# BuzzerSchematic.net
KiCad netlist of a schematic drawn in EAGLE
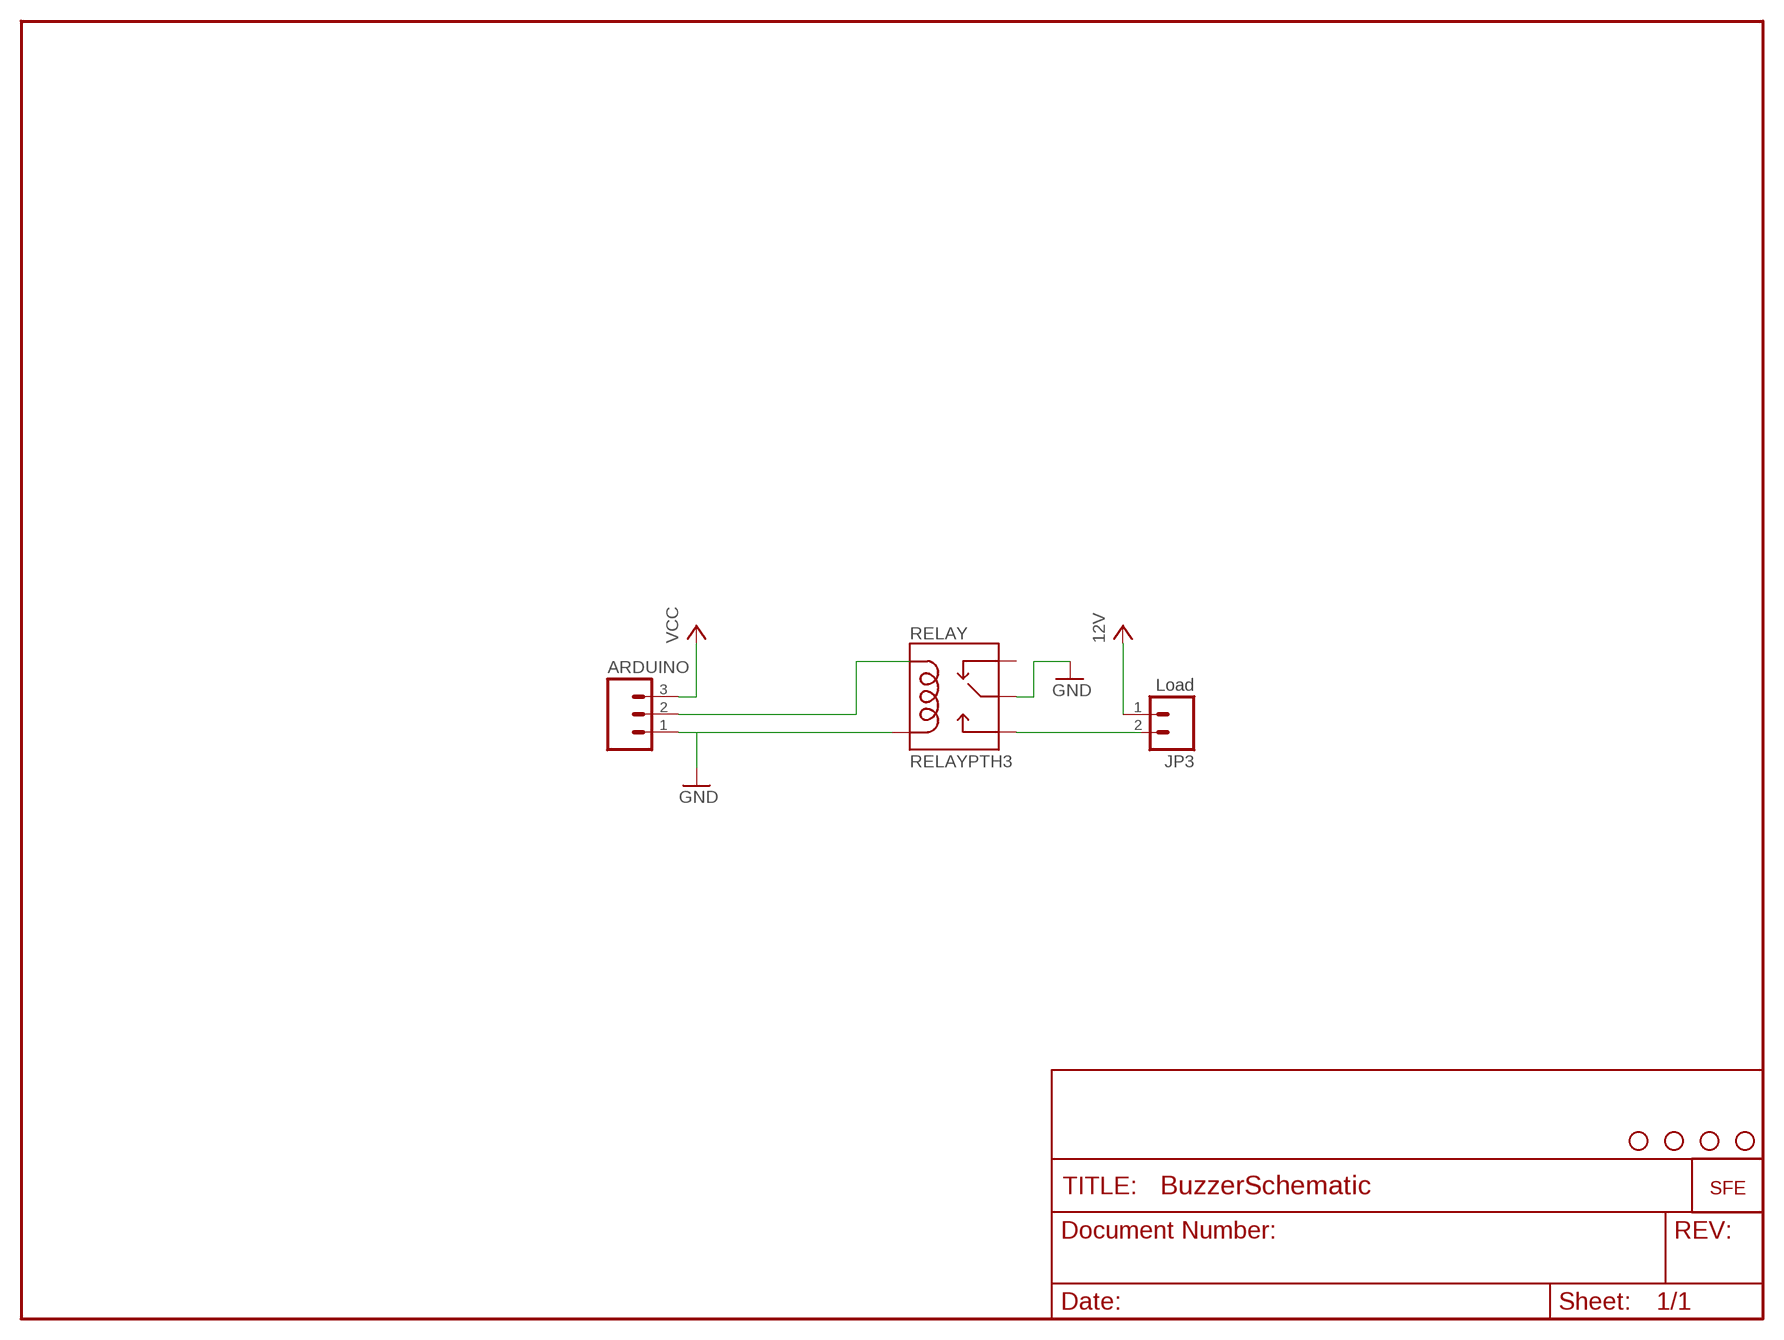
[diagram p0: schematic, sheet 1]

(export (version "E")
  (design (tool "Eeschema 10.0.6"))
  (components
    (comp (ref "ARDUINO")
      (value "M03SCREW")
      (footprint "eagle-import:SCREWTERMINAL-3.5MM-3")
      (libsource (lib "eagle-import") (part "M03SCREW"))
    )
    (comp (ref "JP3")
      (value "Load")
      (footprint "eagle-import:SCREWTERMINAL-5MM-2")
      (libsource (lib "eagle-import") (part "M025MM"))
    )
    (comp (ref "RELAY")
      (value "RELAYPTH3")
      (footprint "eagle-import:RELAY-T9A-2")
      (libsource (lib "eagle-import") (part "RELAYPTH3"))
    )
    (comp (ref "U$1")
      (value "LOGO-SFENEW")
      (footprint "eagle-import:SFE-NEW-WEBLOGO")
      (libsource (lib "eagle-import") (part "LOGO-SFENEW"))
    )
    (comp (ref "U$3")
      (value "STAND-OFF")
      (footprint "eagle-import:STAND-OFF")
      (libsource (lib "eagle-import") (part "STAND-OFF"))
    )
    (comp (ref "U$4")
      (value "STAND-OFF")
      (footprint "eagle-import:STAND-OFF")
      (libsource (lib "eagle-import") (part "STAND-OFF"))
    )
    (comp (ref "U$5")
      (value "STAND-OFF")
      (footprint "eagle-import:STAND-OFF")
      (libsource (lib "eagle-import") (part "STAND-OFF"))
    )
    (comp (ref "U$7")
      (value "STAND-OFF")
      (footprint "eagle-import:STAND-OFF")
      (libsource (lib "eagle-import") (part "STAND-OFF"))
    )
  )
  (nets
    (net (code "1") (name "12V") (class "Default")
      (node (ref "ARDUINO") (pin "3") (pinfunction "3_3") (pintype "passive"))
      (node (ref "JP3") (pin "1") (pinfunction "1_1") (pintype "passive"))
    )
    (net (code "2") (name "GND") (class "Default")
      (node (ref "ARDUINO") (pin "1") (pinfunction "1_1") (pintype "passive"))
      (node (ref "RELAY") (pin "COIL2") (pinfunction "COIL2_COIL2") (pintype "bidirectional"))
      (node (ref "RELAY") (pin "MAIN") (pinfunction "MAIN_MAIN") (pintype "bidirectional"))
    )
    (net (code "3") (name "unconnected-(ARDUINO-Pad2)") (class "Default")
      (node (ref "ARDUINO") (pin "2") (pinfunction "2_2") (pintype "passive"))
    )
    (net (code "4") (name "unconnected-(JP3-Pad2)") (class "Default")
      (node (ref "JP3") (pin "2") (pinfunction "2_2") (pintype "passive"))
    )
    (net (code "5") (name "unconnected-(RELAY-PadCOIL1)") (class "Default")
      (node (ref "RELAY") (pin "COIL1") (pinfunction "COIL1_COIL1") (pintype "bidirectional"))
    )
    (net (code "6") (name "unconnected-(RELAY-PadNC)") (class "Default")
      (node (ref "RELAY") (pin "NC") (pinfunction "NC_NC") (pintype "bidirectional"))
    )
    (net (code "7") (name "unconnected-(RELAY-PadNO)") (class "Default")
      (node (ref "RELAY") (pin "NO") (pinfunction "NO_NO") (pintype "bidirectional"))
    )
  )
)
